# ESP32_Tiny.net
KiCad netlist of a schematic drawn in EAGLE
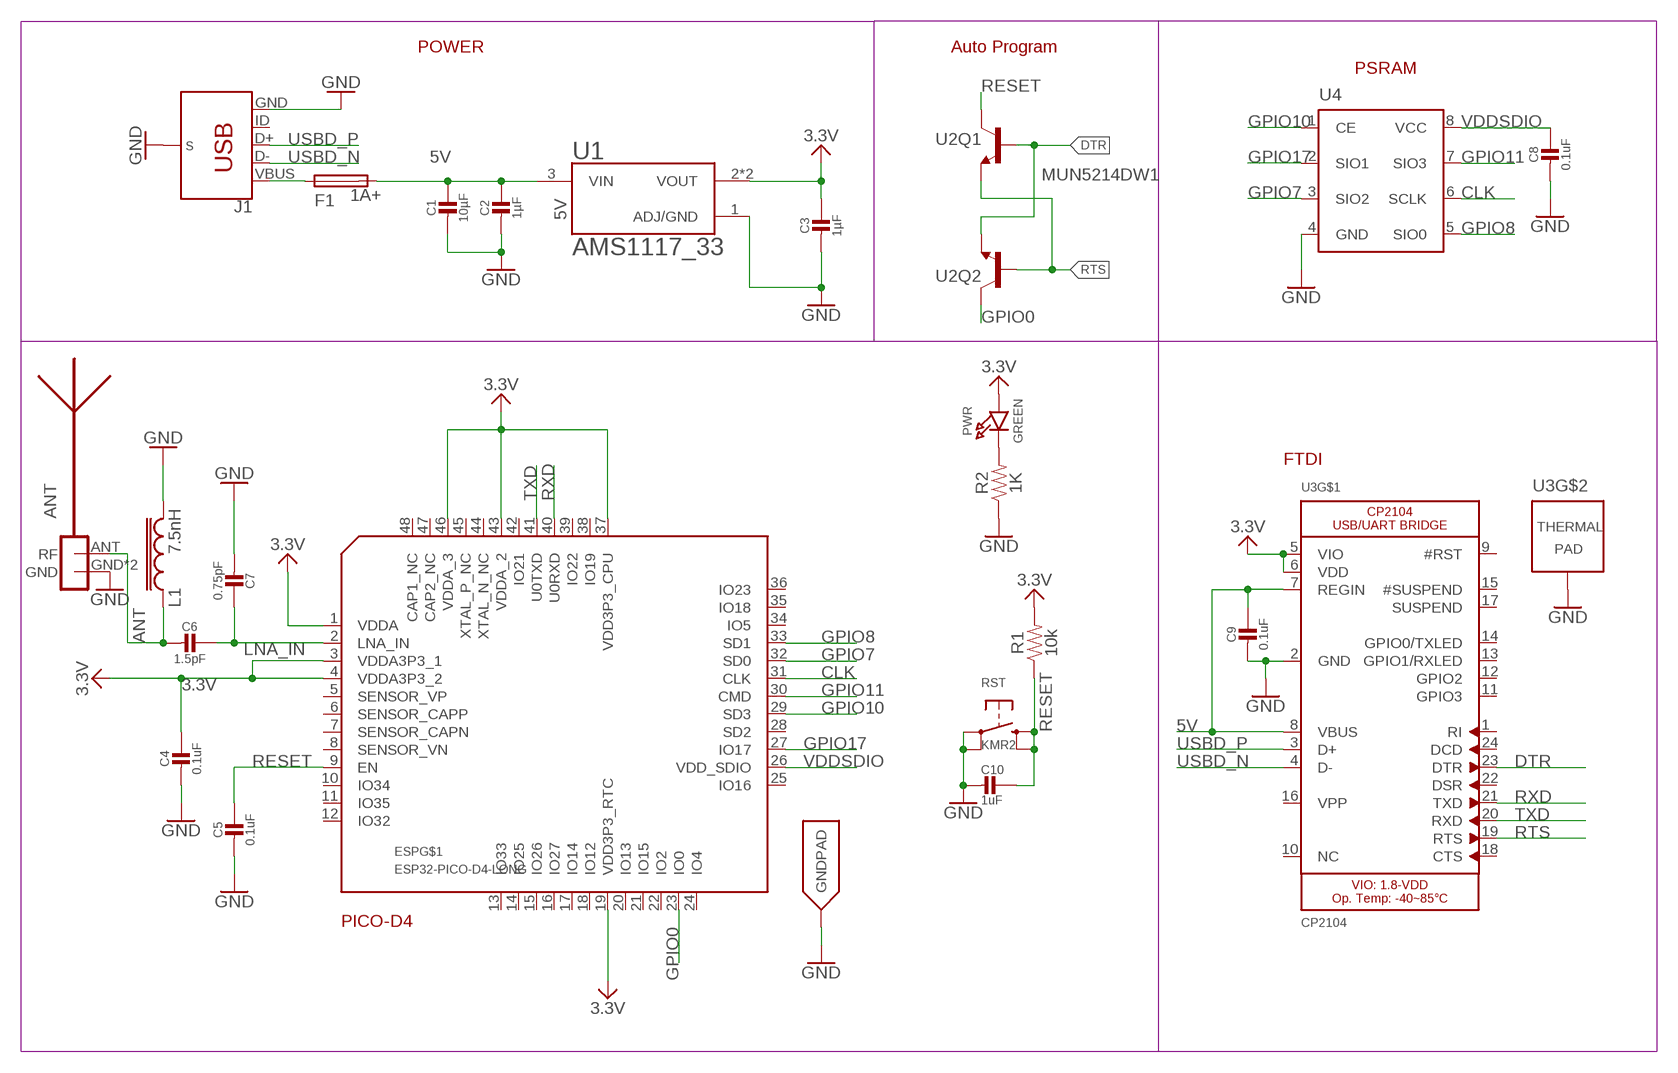
[diagram p0: schematic, sheet 1]

(export (version "E")
  (design (tool "Eeschema 10.0.6"))
  (components
    (comp (ref "ANT")
      (value "AN043_2.45GREV1_RIGHT")
      (footprint "eagle-import:AN043_RIGHT")
      (libsource (lib "eagle-import") (part "AN043_2.45GREV1_RIGHT"))
    )
    (comp (ref "C1")
      (value "10µF")
      (footprint "eagle-import:0805")
      (libsource (lib "eagle-import") (part "CAP_CERAMIC_0805"))
    )
    (comp (ref "C2")
      (value "1µF")
      (footprint "eagle-import:0603")
      (libsource (lib "eagle-import") (part "CAP_CERAMIC_0603"))
    )
    (comp (ref "C3")
      (value "1µF")
      (footprint "eagle-import:0603")
      (libsource (lib "eagle-import") (part "CAP_CERAMIC_0603"))
    )
    (comp (ref "C4")
      (value "0.1uF")
      (footprint "eagle-import:0603")
      (libsource (lib "eagle-import") (part "CAP_CERAMIC_0603"))
    )
    (comp (ref "C5")
      (value "0.1uF")
      (footprint "eagle-import:0603")
      (libsource (lib "eagle-import") (part "CAP_CERAMIC_0603"))
    )
    (comp (ref "C6")
      (value "1.5pF")
      (footprint "eagle-import:0603")
      (libsource (lib "eagle-import") (part "CAP_CERAMIC_0603"))
    )
    (comp (ref "C7")
      (value "0.75pF")
      (footprint "eagle-import:0603")
      (libsource (lib "eagle-import") (part "CAP_CERAMIC_0603"))
    )
    (comp (ref "C8")
      (value "0.1uF")
      (footprint "eagle-import:0603")
      (libsource (lib "eagle-import") (part "CAP_CERAMIC_0603"))
    )
    (comp (ref "C9")
      (value "0.1uF")
      (footprint "eagle-import:0603")
      (libsource (lib "eagle-import") (part "CAP_CERAMIC_0603"))
    )
    (comp (ref "C10")
      (value "1uF")
      (footprint "eagle-import:0603")
      (libsource (lib "eagle-import") (part "CAP_CERAMIC_0603"))
    )
    (comp (ref "ESP")
      (value "ESP32-PICO-D4-LONG")
      (footprint "eagle-import:PICO-D4-QFN48-LONG")
      (libsource (lib "eagle-import") (part "ESP32-PICO-D4-LONG"))
    )
    (comp (ref "F1")
      (value "1A+")
      (footprint "eagle-import:1206")
      (libsource (lib "eagle-import") (part "FUSE-1206"))
    )
    (comp (ref "J1")
      (value "USB-MICRO-B-SOCKET-2")
      (footprint "eagle-import:USB-MICRO-B-SOCKET-2")
      (libsource (lib "eagle-import") (part "USB-MICRO-B-SOCKET-2"))
    )
    (comp (ref "L1")
      (value "7.5nH")
      (footprint "eagle-import:0603")
      (libsource (lib "eagle-import") (part "INDUCTOR-0603"))
    )
    (comp (ref "PWR")
      (value "GREEN")
      (footprint "eagle-import:CHIPLED_0603")
      (libsource (lib "eagle-import") (part "LED0603"))
    )
    (comp (ref "R1")
      (value "10k")
      (footprint "eagle-import:0603")
      (libsource (lib "eagle-import") (part "RESISTOR0603"))
    )
    (comp (ref "R2")
      (value "1K")
      (footprint "eagle-import:0603")
      (libsource (lib "eagle-import") (part "RESISTOR0603"))
    )
    (comp (ref "RST")
      (value "KMR2")
      (footprint "eagle-import:BTN_KMR2_4.6X2.8")
      (libsource (lib "eagle-import") (part "SWITCH_TACT_SMT4.6X2.8"))
    )
    (comp (ref "U1")
      (value "AMS1117_33")
      (footprint "eagle-import:SOT89")
      (libsource (lib "eagle-import") (part "VREG_AMS1117SMALL"))
    )
    (comp (ref "U2")
      (value "MUN5214DW1")
      (footprint "eagle-import:DUAL_NPN_SC70-6")
      (libsource (lib "eagle-import") (part "NPN_MBT3904DW1T1"))
    )
    (comp (ref "U3")
      (value "CP2104")
      (footprint "eagle-import:QFN24_4MM_SMSC_LONG")
      (libsource (lib "eagle-import") (part "FTDI_CP2104LONG"))
    )
    (comp (ref "U4")
      (value "LY68L6400SLIT")
      (footprint "eagle-import:SOP8")
      (libsource (lib "eagle-import") (part "PSRAM_LY68L6400SLIT"))
    )
  )
  (nets
    (net (code "1") (name "/5V") (class "Default")
      (node (ref "C1") (pin "1") (pinfunction "1_1") (pintype "passive"))
      (node (ref "C2") (pin "1") (pinfunction "1_1") (pintype "passive"))
      (node (ref "C9") (pin "1") (pinfunction "1_1") (pintype "passive"))
      (node (ref "F1") (pin "2") (pinfunction "2_2") (pintype "passive"))
      (node (ref "U1") (pin "3") (pinfunction "VIN_3") (pintype "input"))
      (node (ref "U3") (pin "7") (pinfunction "REGIN_7") (pintype "input"))
      (node (ref "U3") (pin "8") (pinfunction "VBUS_8") (pintype "input"))
    )
    (net (code "2") (name "/ANT") (class "Default")
      (node (ref "ANT") (pin "ANT") (pinfunction "RF_ANT") (pintype "bidirectional"))
      (node (ref "C6") (pin "2") (pinfunction "2_2") (pintype "passive"))
      (node (ref "L1") (pin "1") (pinfunction "P$1_1") (pintype "passive"))
    )
    (net (code "3") (name "/CLK") (class "Default")
      (node (ref "ESP") (pin "31") (pinfunction "CLK_31") (pintype "bidirectional"))
      (node (ref "U4") (pin "6") (pinfunction "SCLK_6") (pintype "passive"))
    )
    (net (code "4") (name "/GPIO0") (class "Default")
      (node (ref "ESP") (pin "23") (pinfunction "IO0_23") (pintype "bidirectional"))
      (node (ref "U2") (pin "6") (pinfunction "C_6") (pintype "passive"))
    )
    (net (code "5") (name "/GPIO7") (class "Default")
      (node (ref "ESP") (pin "32") (pinfunction "SD0_32") (pintype "bidirectional"))
      (node (ref "U4") (pin "3") (pinfunction "SIO2_3") (pintype "input"))
    )
    (net (code "6") (name "/GPIO8") (class "Default")
      (node (ref "ESP") (pin "33") (pinfunction "SD1_33") (pintype "bidirectional"))
      (node (ref "U4") (pin "5") (pinfunction "SIO0_5") (pintype "input"))
    )
    (net (code "7") (name "/GPIO10") (class "Default")
      (node (ref "ESP") (pin "29") (pinfunction "SD3_29") (pintype "bidirectional"))
      (node (ref "U4") (pin "1") (pinfunction "CE_1") (pintype "output"))
    )
    (net (code "8") (name "/GPIO11") (class "Default")
      (node (ref "ESP") (pin "30") (pinfunction "CMD_30") (pintype "bidirectional"))
      (node (ref "U4") (pin "7") (pinfunction "SIO3_7") (pintype "output"))
    )
    (net (code "9") (name "/GPIO17") (class "Default")
      (node (ref "ESP") (pin "27") (pinfunction "IO17_27") (pintype "bidirectional"))
      (node (ref "U4") (pin "2") (pinfunction "SIO1_2") (pintype "input"))
    )
    (net (code "10") (name "/LNA_IN") (class "Default")
      (node (ref "C6") (pin "1") (pinfunction "1_1") (pintype "passive"))
      (node (ref "C7") (pin "1") (pinfunction "1_1") (pintype "passive"))
      (node (ref "ESP") (pin "2") (pinfunction "LNA_IN_2") (pintype "bidirectional"))
    )
    (net (code "11") (name "/RESET") (class "Default")
      (node (ref "C10") (pin "1") (pinfunction "1_1") (pintype "passive"))
      (node (ref "C5") (pin "1") (pinfunction "1_1") (pintype "passive"))
      (node (ref "ESP") (pin "9") (pinfunction "EN_9") (pintype "bidirectional"))
      (node (ref "R1") (pin "1") (pinfunction "1_1") (pintype "passive"))
      (node (ref "RST") (pin "B") (pinfunction "S_B") (pintype "passive"))
      (node (ref "RST") (pin "B'") (pinfunction "S1_B'") (pintype "passive"))
      (node (ref "U2") (pin "3") (pinfunction "C_3") (pintype "passive"))
    )
    (net (code "12") (name "/RXD") (class "Default")
      (node (ref "ESP") (pin "40") (pinfunction "U0RXD_40") (pintype "bidirectional"))
      (node (ref "U3") (pin "21") (pinfunction "TXD_21") (pintype "output"))
    )
    (net (code "13") (name "/TXD") (class "Default")
      (node (ref "ESP") (pin "41") (pinfunction "U0TXD_41") (pintype "bidirectional"))
      (node (ref "U3") (pin "20") (pinfunction "RXD_20") (pintype "input"))
    )
    (net (code "14") (name "/USBD_N") (class "Default")
      (node (ref "J1") (pin "D-") (pinfunction "D-_D-") (pintype "bidirectional"))
      (node (ref "U3") (pin "4") (pinfunction "D-_4") (pintype "bidirectional"))
    )
    (net (code "15") (name "/USBD_P") (class "Default")
      (node (ref "J1") (pin "D+") (pinfunction "D+_D+") (pintype "bidirectional"))
      (node (ref "U3") (pin "3") (pinfunction "D+_3") (pintype "bidirectional"))
    )
    (net (code "16") (name "/VDDSDIO") (class "Default")
      (node (ref "C8") (pin "1") (pinfunction "1_1") (pintype "passive"))
      (node (ref "ESP") (pin "26") (pinfunction "VDD_SDIO_26") (pintype "output"))
      (node (ref "U4") (pin "8") (pinfunction "VCC_8") (pintype "input"))
    )
    (net (code "17") (name "DTR") (class "Default")
      (node (ref "U2") (pin "1") (pinfunction "E_1") (pintype "passive"))
      (node (ref "U2") (pin "5") (pinfunction "B_5") (pintype "passive"))
      (node (ref "U3") (pin "23") (pinfunction "DTR_23") (pintype "bidirectional"))
    )
    (net (code "18") (name "Net-(F1-Pad1)") (class "Default")
      (node (ref "F1") (pin "1") (pinfunction "1_1") (pintype "passive"))
      (node (ref "J1") (pin "VBUS") (pinfunction "VBUS_VBUS") (pintype "passive"))
    )
    (net (code "19") (name "Net-(PWR-PadC)") (class "Default")
      (node (ref "PWR") (pin "C") (pinfunction "C_C") (pintype "passive"))
      (node (ref "R2") (pin "2") (pinfunction "2_2") (pintype "passive"))
    )
    (net (code "20") (name "RTS") (class "Default")
      (node (ref "U2") (pin "2") (pinfunction "B_2") (pintype "passive"))
      (node (ref "U2") (pin "4") (pinfunction "E_4") (pintype "passive"))
      (node (ref "U3") (pin "19") (pinfunction "RTS_19") (pintype "bidirectional"))
    )
    (net (code "21") (name "SUPPLY_3.3V") (class "Default")
      (node (ref "C3") (pin "1") (pinfunction "1_1") (pintype "passive"))
      (node (ref "C4") (pin "1") (pinfunction "1_1") (pintype "passive"))
      (node (ref "ESP") (pin "1") (pinfunction "VDDA_1") (pintype "input"))
      (node (ref "ESP") (pin "19") (pinfunction "VDD3P3_RTC_19") (pintype "input"))
      (node (ref "ESP") (pin "3") (pinfunction "VDDA3P3_1_3") (pintype "input"))
      (node (ref "ESP") (pin "37") (pinfunction "VDD3P3_CPU_37") (pintype "input"))
      (node (ref "ESP") (pin "4") (pinfunction "VDDA3P3_2_4") (pintype "input"))
      (node (ref "ESP") (pin "43") (pinfunction "VDDA_2_43") (pintype "input"))
      (node (ref "ESP") (pin "46") (pinfunction "VDDA_3_46") (pintype "input"))
      (node (ref "PWR") (pin "A") (pinfunction "A_A") (pintype "passive"))
      (node (ref "R1") (pin "2") (pinfunction "2_2") (pintype "passive"))
      (node (ref "U1") (pin "2") (pinfunction "VOUT_2") (pintype "passive"))
      (node (ref "U1") (pin "2@1") (pinfunction "VOUT_2@1") (pintype "passive"))
      (node (ref "U3") (pin "5") (pinfunction "VIO_5") (pintype "input"))
      (node (ref "U3") (pin "6") (pinfunction "VDD_6") (pintype "input"))
    )
    (net (code "22") (name "SUPPLY_GND") (class "Default")
      (node (ref "ANT") (pin "GND") (pinfunction "GND_GND") (pintype "passive"))
      (node (ref "ANT") (pin "GND-PAD1") (pinfunction "GND_GND-PAD1") (pintype "passive"))
      (node (ref "C1") (pin "2") (pinfunction "2_2") (pintype "passive"))
      (node (ref "C10") (pin "2") (pinfunction "2_2") (pintype "passive"))
      (node (ref "C2") (pin "2") (pinfunction "2_2") (pintype "passive"))
      (node (ref "C3") (pin "2") (pinfunction "2_2") (pintype "passive"))
      (node (ref "C4") (pin "2") (pinfunction "2_2") (pintype "passive"))
      (node (ref "C5") (pin "2") (pinfunction "2_2") (pintype "passive"))
      (node (ref "C7") (pin "2") (pinfunction "2_2") (pintype "passive"))
      (node (ref "C8") (pin "2") (pinfunction "2_2") (pintype "passive"))
      (node (ref "C9") (pin "2") (pinfunction "2_2") (pintype "passive"))
      (node (ref "ESP") (pin "EXP") (pinfunction "GNDPAD_EXP") (pintype "passive"))
      (node (ref "J1") (pin "GND") (pinfunction "GND_GND") (pintype "passive"))
      (node (ref "J1") (pin "S1") (pinfunction "SHIELD_S1") (pintype "bidirectional"))
      (node (ref "J1") (pin "S2") (pinfunction "SHIELD_S2") (pintype "bidirectional"))
      (node (ref "J1") (pin "S3") (pinfunction "SHIELD_S3") (pintype "bidirectional"))
      (node (ref "J1") (pin "S4") (pinfunction "SHIELD_S4") (pintype "bidirectional"))
      (node (ref "J1") (pin "S5") (pinfunction "SHIELD_S5") (pintype "bidirectional"))
      (node (ref "L1") (pin "2") (pinfunction "P$2_2") (pintype "passive"))
      (node (ref "R2") (pin "1") (pinfunction "1_1") (pintype "passive"))
      (node (ref "RST") (pin "A") (pinfunction "P_A") (pintype "passive"))
      (node (ref "RST") (pin "A'") (pinfunction "P1_A'") (pintype "passive"))
      (node (ref "U1") (pin "1") (pinfunction "ADJ/GND_1") (pintype "passive"))
      (node (ref "U3") (pin "2") (pinfunction "GND_2") (pintype "input"))
      (node (ref "U3") (pin "THERM") (pinfunction "TP_THERM") (pintype "passive"))
      (node (ref "U4") (pin "4") (pinfunction "GND_4") (pintype "input"))
    )
    (net (code "23") (name "unconnected-(ESPA-CAP1_NC-Pad48)") (class "Default")
      (node (ref "ESP") (pin "48") (pinfunction "CAP1_NC_48") (pintype "no_connect"))
    )
    (net (code "24") (name "unconnected-(ESPA-CAP2_NC-Pad47)") (class "Default")
      (node (ref "ESP") (pin "47") (pinfunction "CAP2_NC_47") (pintype "no_connect"))
    )
    (net (code "25") (name "unconnected-(ESPA-IO2-Pad22)") (class "Default")
      (node (ref "ESP") (pin "22") (pinfunction "IO2_22") (pintype "bidirectional"))
    )
    (net (code "26") (name "unconnected-(ESPA-IO4-Pad24)") (class "Default")
      (node (ref "ESP") (pin "24") (pinfunction "IO4_24") (pintype "bidirectional"))
    )
    (net (code "27") (name "unconnected-(ESPA-IO5-Pad34)") (class "Default")
      (node (ref "ESP") (pin "34") (pinfunction "IO5_34") (pintype "bidirectional"))
    )
    (net (code "28") (name "unconnected-(ESPA-IO12-Pad18)") (class "Default")
      (node (ref "ESP") (pin "18") (pinfunction "IO12_18") (pintype "bidirectional"))
    )
    (net (code "29") (name "unconnected-(ESPA-IO13-Pad20)") (class "Default")
      (node (ref "ESP") (pin "20") (pinfunction "IO13_20") (pintype "bidirectional"))
    )
    (net (code "30") (name "unconnected-(ESPA-IO14-Pad17)") (class "Default")
      (node (ref "ESP") (pin "17") (pinfunction "IO14_17") (pintype "bidirectional"))
    )
    (net (code "31") (name "unconnected-(ESPA-IO15-Pad21)") (class "Default")
      (node (ref "ESP") (pin "21") (pinfunction "IO15_21") (pintype "bidirectional"))
    )
    (net (code "32") (name "unconnected-(ESPA-IO16-Pad25)") (class "Default")
      (node (ref "ESP") (pin "25") (pinfunction "IO16_25") (pintype "bidirectional"))
    )
    (net (code "33") (name "unconnected-(ESPA-IO18-Pad35)") (class "Default")
      (node (ref "ESP") (pin "35") (pinfunction "IO18_35") (pintype "bidirectional"))
    )
    (net (code "34") (name "unconnected-(ESPA-IO19-Pad38)") (class "Default")
      (node (ref "ESP") (pin "38") (pinfunction "IO19_38") (pintype "bidirectional"))
    )
    (net (code "35") (name "unconnected-(ESPA-IO21-Pad42)") (class "Default")
      (node (ref "ESP") (pin "42") (pinfunction "IO21_42") (pintype "bidirectional"))
    )
    (net (code "36") (name "unconnected-(ESPA-IO22-Pad39)") (class "Default")
      (node (ref "ESP") (pin "39") (pinfunction "IO22_39") (pintype "bidirectional"))
    )
    (net (code "37") (name "unconnected-(ESPA-IO23-Pad36)") (class "Default")
      (node (ref "ESP") (pin "36") (pinfunction "IO23_36") (pintype "bidirectional"))
    )
    (net (code "38") (name "unconnected-(ESPA-IO25-Pad14)") (class "Default")
      (node (ref "ESP") (pin "14") (pinfunction "IO25_14") (pintype "bidirectional"))
    )
    (net (code "39") (name "unconnected-(ESPA-IO26-Pad15)") (class "Default")
      (node (ref "ESP") (pin "15") (pinfunction "IO26_15") (pintype "bidirectional"))
    )
    (net (code "40") (name "unconnected-(ESPA-IO27-Pad16)") (class "Default")
      (node (ref "ESP") (pin "16") (pinfunction "IO27_16") (pintype "bidirectional"))
    )
    (net (code "41") (name "unconnected-(ESPA-IO32-Pad12)") (class "Default")
      (node (ref "ESP") (pin "12") (pinfunction "IO32_12") (pintype "bidirectional"))
    )
    (net (code "42") (name "unconnected-(ESPA-IO33-Pad13)") (class "Default")
      (node (ref "ESP") (pin "13") (pinfunction "IO33_13") (pintype "bidirectional"))
    )
    (net (code "43") (name "unconnected-(ESPA-IO34-Pad10)") (class "Default")
      (node (ref "ESP") (pin "10") (pinfunction "IO34_10") (pintype "bidirectional"))
    )
    (net (code "44") (name "unconnected-(ESPA-IO35-Pad11)") (class "Default")
      (node (ref "ESP") (pin "11") (pinfunction "IO35_11") (pintype "bidirectional"))
    )
    (net (code "45") (name "unconnected-(ESPA-SD2-Pad28)") (class "Default")
      (node (ref "ESP") (pin "28") (pinfunction "SD2_28") (pintype "bidirectional"))
    )
    (net (code "46") (name "unconnected-(ESPA-SENSOR_CAPN-Pad7)") (class "Default")
      (node (ref "ESP") (pin "7") (pinfunction "SENSOR_CAPN_7") (pintype "bidirectional"))
    )
    (net (code "47") (name "unconnected-(ESPA-SENSOR_CAPP-Pad6)") (class "Default")
      (node (ref "ESP") (pin "6") (pinfunction "SENSOR_CAPP_6") (pintype "bidirectional"))
    )
    (net (code "48") (name "unconnected-(ESPA-SENSOR_VN-Pad8)") (class "Default")
      (node (ref "ESP") (pin "8") (pinfunction "SENSOR_VN_8") (pintype "bidirectional"))
    )
    (net (code "49") (name "unconnected-(ESPA-SENSOR_VP-Pad5)") (class "Default")
      (node (ref "ESP") (pin "5") (pinfunction "SENSOR_VP_5") (pintype "bidirectional"))
    )
    (net (code "50") (name "unconnected-(ESPA-XTAL_N_NC-Pad44)") (class "Default")
      (node (ref "ESP") (pin "44") (pinfunction "XTAL_N_NC_44") (pintype "no_connect"))
    )
    (net (code "51") (name "unconnected-(ESPA-XTAL_P_NC-Pad45)") (class "Default")
      (node (ref "ESP") (pin "45") (pinfunction "XTAL_P_NC_45") (pintype "no_connect"))
    )
    (net (code "52") (name "unconnected-(J1-PadID)") (class "Default")
      (node (ref "J1") (pin "ID") (pinfunction "ID_ID") (pintype "bidirectional"))
    )
    (net (code "53") (name "unconnected-(U3A-#RST-Pad9)") (class "Default")
      (node (ref "U3") (pin "9") (pinfunction "#RST_9") (pintype "bidirectional"))
    )
    (net (code "54") (name "unconnected-(U3A-#SUSPEND-Pad15)") (class "Default")
      (node (ref "U3") (pin "15") (pinfunction "#SUSPEND_15") (pintype "output"))
    )
    (net (code "55") (name "unconnected-(U3A-CTS-Pad18)") (class "Default")
      (node (ref "U3") (pin "18") (pinfunction "CTS_18") (pintype "bidirectional"))
    )
    (net (code "56") (name "unconnected-(U3A-DCD-Pad24)") (class "Default")
      (node (ref "U3") (pin "24") (pinfunction "DCD_24") (pintype "bidirectional"))
    )
    (net (code "57") (name "unconnected-(U3A-DSR-Pad22)") (class "Default")
      (node (ref "U3") (pin "22") (pinfunction "DSR_22") (pintype "bidirectional"))
    )
    (net (code "58") (name "unconnected-(U3A-GPIO0{slash}TXLED-Pad14)") (class "Default")
      (node (ref "U3") (pin "14") (pinfunction "GPIO0/TXLED_14") (pintype "bidirectional"))
    )
    (net (code "59") (name "unconnected-(U3A-GPIO1{slash}RXLED-Pad13)") (class "Default")
      (node (ref "U3") (pin "13") (pinfunction "GPIO1/RXLED_13") (pintype "bidirectional"))
    )
    (net (code "60") (name "unconnected-(U3A-GPIO2-Pad12)") (class "Default")
      (node (ref "U3") (pin "12") (pinfunction "GPIO2_12") (pintype "bidirectional"))
    )
    (net (code "61") (name "unconnected-(U3A-GPIO3-Pad11)") (class "Default")
      (node (ref "U3") (pin "11") (pinfunction "GPIO3_11") (pintype "bidirectional"))
    )
    (net (code "62") (name "unconnected-(U3A-NC-Pad10)") (class "Default")
      (node (ref "U3") (pin "10") (pinfunction "NC_10") (pintype "no_connect"))
    )
    (net (code "63") (name "unconnected-(U3A-RI-Pad1)") (class "Default")
      (node (ref "U3") (pin "1") (pinfunction "RI_1") (pintype "bidirectional"))
    )
    (net (code "64") (name "unconnected-(U3A-SUSPEND-Pad17)") (class "Default")
      (node (ref "U3") (pin "17") (pinfunction "SUSPEND_17") (pintype "output"))
    )
    (net (code "65") (name "unconnected-(U3A-VPP-Pad16)") (class "Default")
      (node (ref "U3") (pin "16") (pinfunction "VPP_16") (pintype "bidirectional"))
    )
  )
)
